# 04_POWER.net
KiCad netlist of a schematic drawn in Altium Designer
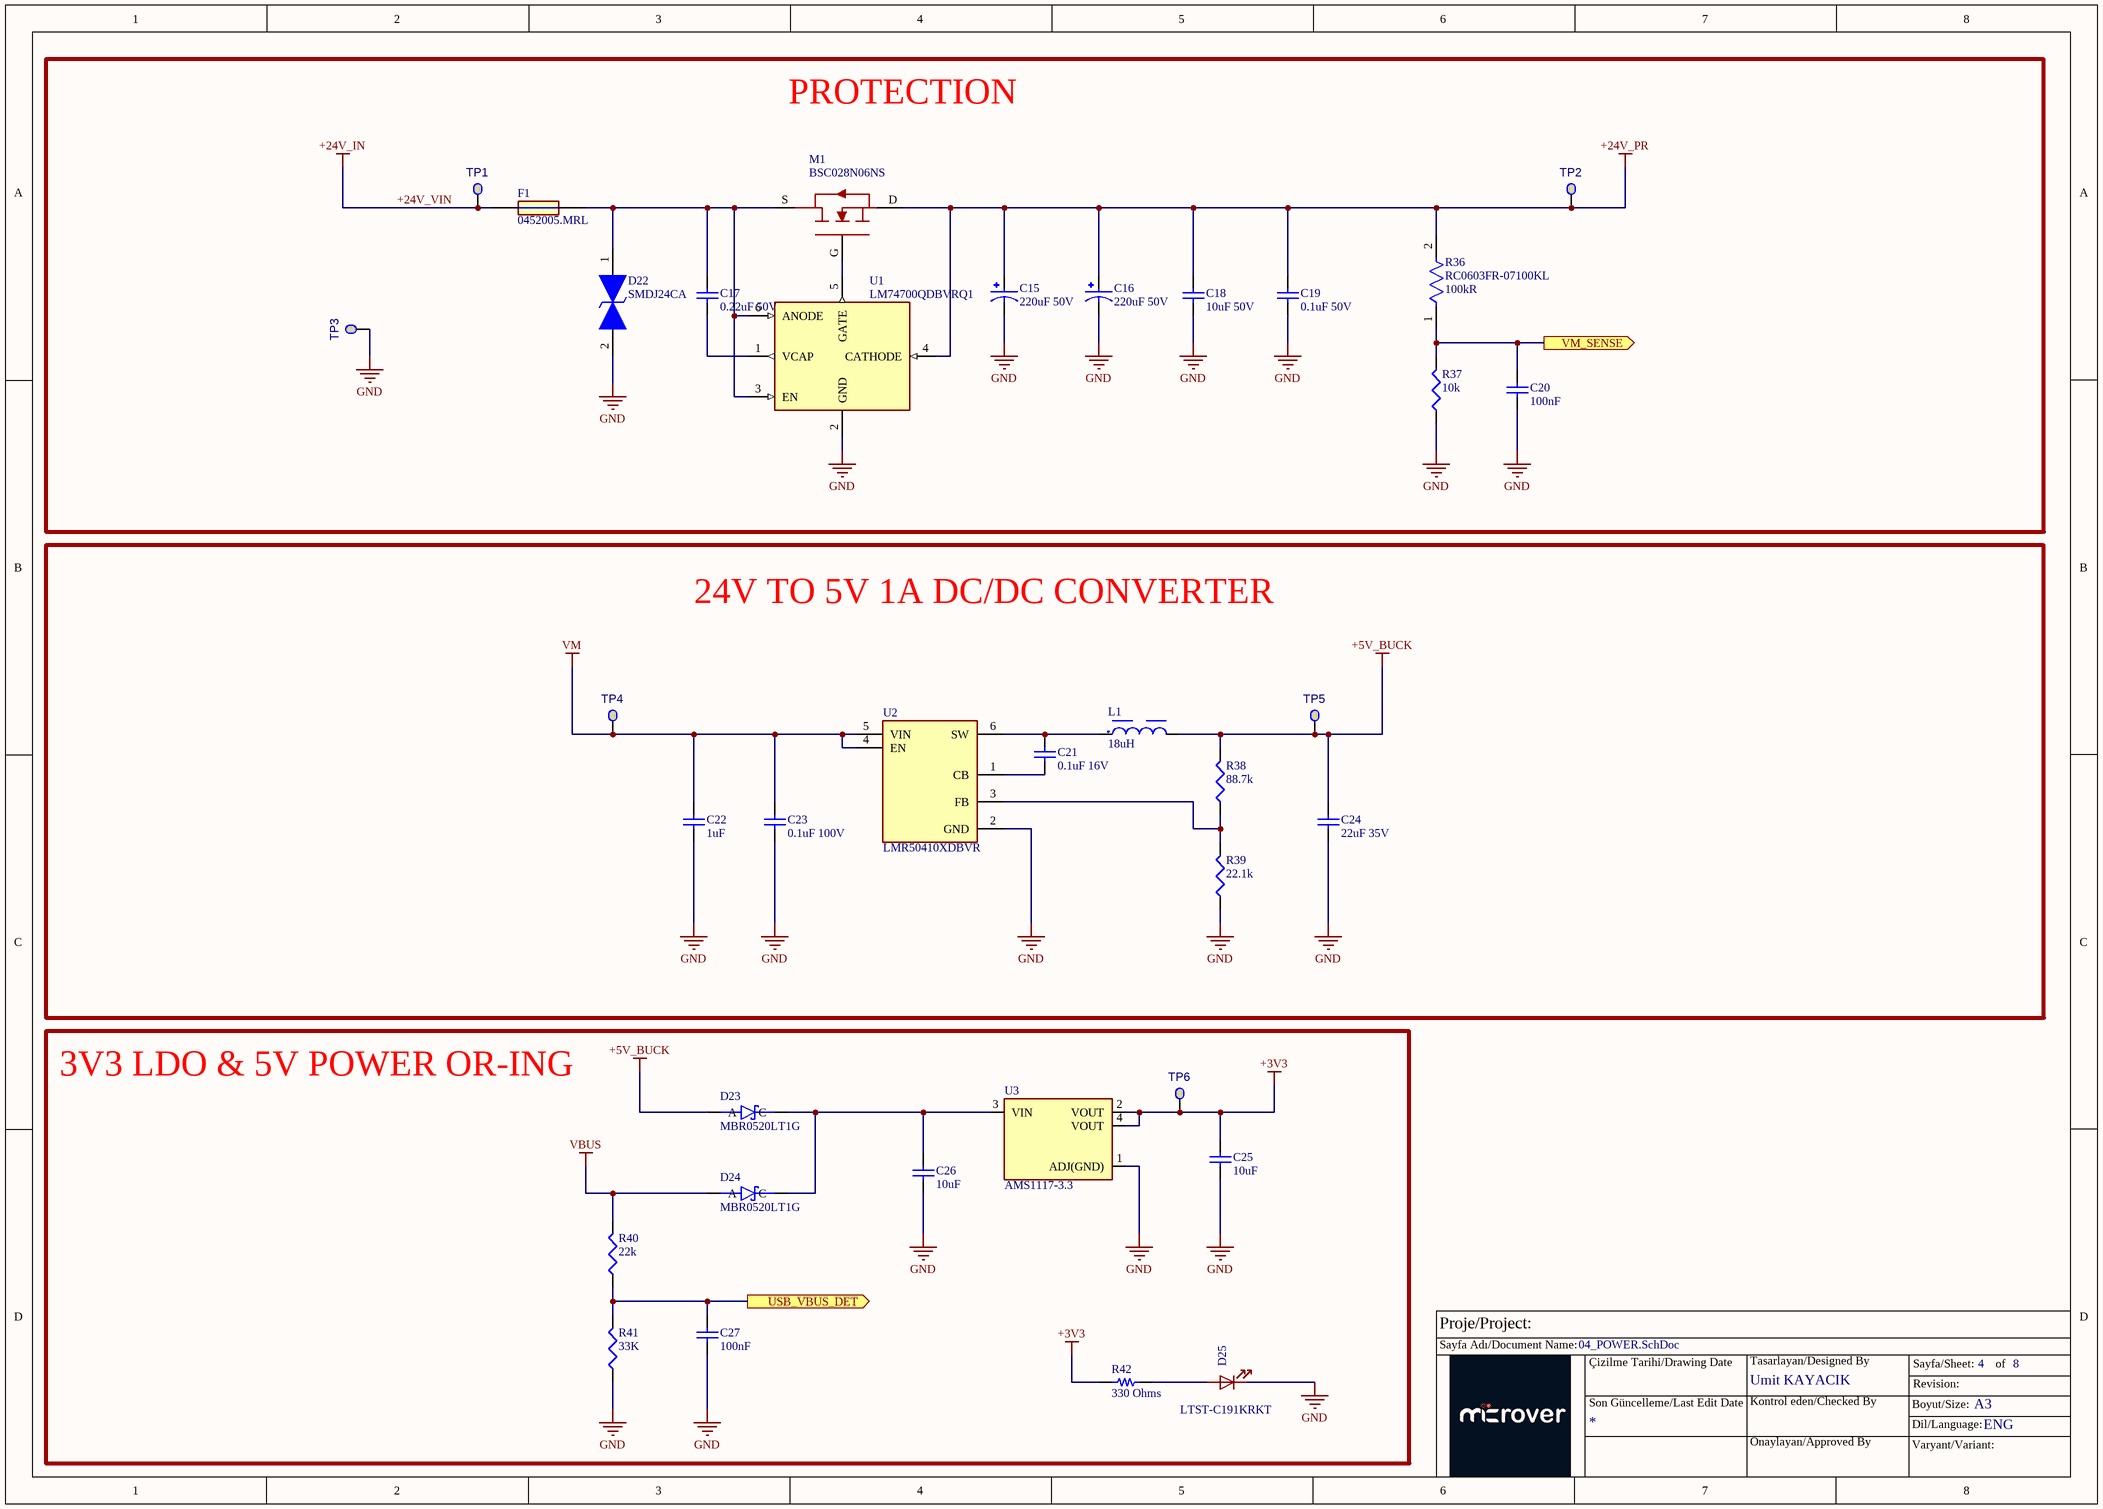
[diagram p0: 04_POWER.SchDoc]

(export (version "E")
  (design (tool "Eeschema 10.0.6"))
  (components
    (comp (ref "C15")
      (value "220uF 50V")
      (footprint "CAP_EEEFT1H221AV")
      (description "220 µF 50 V Aluminum Electrolytic Capacitors Radial, Can - SMD 180mOhm @ 100kHz 2000 Hrs @ 105°C")
      (fields
        (field (name "MANUFACTURER PART NUMBER") "EEE-FT1H221AV")
        (field (name "MF") "Panasonic Electronic Components")
      )
      (libsource (lib "HW_ADHERENT_LANECTRL_R1") (part "EEEFT1H221AV"))
    )
    (comp (ref "C16")
      (value "220uF 50V")
      (footprint "CAP_EEEFT1H221AV")
      (description "220 µF 50 V Aluminum Electrolytic Capacitors Radial, Can - SMD 180mOhm @ 100kHz 2000 Hrs @ 105°C")
      (fields
        (field (name "MANUFACTURER PART NUMBER") "EEE-FT1H221AV")
        (field (name "MF") "Panasonic Electronic Components")
      )
      (libsource (lib "HW_ADHERENT_LANECTRL_R1") (part "EEEFT1H221AV"))
    )
    (comp (ref "C17")
      (value "0.22uF 50V")
      (footprint "SMC0603")
      (description "0.22 µF ±10% 50V Ceramic Capacitor X7R 0603 (1608 Metric)")
      (fields
        (field (name "MANUFACTURER PART NUMBER") "GCM188R71H224KA64D")
        (field (name "Comment") "CAP CER 0.22UF 50V X7R 0603")
      )
      (libsource (lib "HW_ADHERENT_LANECTRL_R1") (part "CAP0603_0.22UF_50V"))
    )
    (comp (ref "C18")
      (value "10uF 50V")
      (footprint "SMC1206")
      (description "10 µF ±10% 50V Ceramic Capacitor X5R 1206 (3216 Metric)")
      (fields
        (field (name "MANUFACTURER PART NUMBER") "CL31A106KBHNNNE")
        (field (name "LCSC PART NUMBER") "C13585")
      )
      (libsource (lib "HW_ADHERENT_LANECTRL_R1") (part "CAP1206_10UF_50V"))
    )
    (comp (ref "C19")
      (value "0.1uF 50V")
      (footprint "SMC0603")
      (description "0.1 µF ±10% 50V Ceramic Capacitor X7R 0603 (1608 Metric)")
      (fields
        (field (name "MANUFACTURER PART NUMBER") "CL10B104KB8NNNL")
        (field (name "LCSC PART NUMBER") "C1591")
      )
      (libsource (lib "HW_ADHERENT_LANECTRL_R1") (part "CAP0603_0.1UF_50V_2"))
    )
    (comp (ref "C20")
      (value "100nF")
      (footprint "CAP0603")
      (description "0.1 µF ±10% 50V Ceramic Capacitor X7R 0603 (1608 Metric)")
      (fields
        (field (name "MANUFACTURER PART NUMBER") "CL10B104KA8NNNC")
        (field (name "LCSC PART NUMBER") "C1590")
      )
      (libsource (lib "HW_ADHERENT_LANECTRL_R1") (part "CAP0603_100nF"))
    )
    (comp (ref "C21")
      (value "0.1uF 16V")
      (footprint "CAP0603")
      (description "0.1 µF ±20% 16V Ceramic Capacitor X7R 0603 (1608 Metric)")
      (libsource (lib "HW_ADHERENT_LANECTRL_R1") (part "C0603C104M4RACTU"))
    )
    (comp (ref "C22")
      (value "1uF")
      (footprint "CAP0603")
      (description "CAP CER 1UF 50V X5R 0603")
      (fields (field (name "MANUFACTURER") "Taiyo Yuden"))
      (libsource (lib "HW_ADHERENT_LANECTRL_R1") (part "MSASU168SB5105MTNA01"))
    )
    (comp (ref "C23")
      (value "0.1uF 100V")
      (footprint "CAP0603")
      (description "CAP CER 0.1UF 100V X7R 0603")
      (libsource (lib "HW_ADHERENT_LANECTRL_R1") (part "GRM188R72A104KA35D"))
    )
    (comp (ref "C24")
      (value "22uF 35V")
      (footprint "CAP1206")
      (description "22 µF ±20% 35V Ceramic Capacitor X5R 1206 (3216 Metric)")
      (fields (field (name "MANUFACTURER PART NUMBER") "C3216X5R1V226M160AC"))
      (libsource (lib "HW_ADHERENT_LANECTRL_R1") (part "CAP1206_22uF_35V"))
    )
    (comp (ref "C25")
      (value "10uF")
      (footprint "CAP0603")
      (description "10 µF ±10% 25V Ceramic Capacitor X5R 0603 (1608 Metric)")
      (fields (field (name "MANUFACTURER PART NUMBER") "GRM188R61E106KA73J"))
      (libsource (lib "HW_ADHERENT_LANECTRL_R1") (part "CAP0603_10uF_25V"))
    )
    (comp (ref "C26")
      (value "10uF")
      (footprint "CAP0603")
      (description "10 µF ±10% 25V Ceramic Capacitor X5R 0603 (1608 Metric)")
      (fields (field (name "MANUFACTURER PART NUMBER") "GRM188R61E106KA73J"))
      (libsource (lib "HW_ADHERENT_LANECTRL_R1") (part "CAP0603_10uF_25V"))
    )
    (comp (ref "C27")
      (value "100nF")
      (footprint "CAP0603")
      (description "0.1 µF ±10% 50V Ceramic Capacitor X7R 0603 (1608 Metric)")
      (fields
        (field (name "MANUFACTURER PART NUMBER") "CL10B104KA8NNNC")
        (field (name "LCSC PART NUMBER") "C1590")
      )
      (libsource (lib "HW_ADHERENT_LANECTRL_R1") (part "CAP0603_100nF"))
    )
    (comp (ref "D22")
      (value "SMDJ24CA")
      (footprint "DIONM9059X262N")
      (description "38.9V Clamp 77.1A Ipp Tvs Diode Surface Mount DO-214AB (SMCJ)")
      (fields (field (name "MANUFACTURER") "Littelfuse Inc."))
      (libsource (lib "HW_ADHERENT_LANECTRL_R1") (part "SMDJ24CA"))
    )
    (comp (ref "D23")
      (value "MBR0520LT1G")
      (footprint "SOD3716X135N")
      (description "Diode 20 V 500mA Surface Mount SOD-123")
      (libsource (lib "HW_ADHERENT_LANECTRL_R1") (part "MBR0520LT1G"))
    )
    (comp (ref "D24")
      (value "MBR0520LT1G")
      (footprint "SOD3716X135N")
      (description "Diode 20 V 500mA Surface Mount SOD-123")
      (libsource (lib "HW_ADHERENT_LANECTRL_R1") (part "MBR0520LT1G"))
    )
    (comp (ref "D25")
      (value "LTST-C191KRKT")
      (footprint "LED0603")
      (description "LED RED CLEAR SMD")
      (fields (field (name "MANUFACTURER") "Lite-On Inc."))
      (libsource (lib "HW_ADHERENT_LANECTRL_R1") (part "LED_1"))
    )
    (comp (ref "F1")
      (value "0452005.MRL")
      (footprint "FUSC6127X294N")
      (description "FUSE BRD MNT 5A 125VAC/VDC 2SMD")
      (fields (field (name "MANUFACTURER") "Littelfuse"))
      (libsource (lib "HW_ADHERENT_LANECTRL_R1") (part "0452005.MRL"))
    )
    (comp (ref "L1")
      (value "18uH")
      (footprint "WE-LQS_6045")
      (description "18 µH Semi-Shielded Drum Core, Wirewound Inductor 2.2 A 81mOhm Nonstandard")
      (libsource (lib "HW_ADHERENT_LANECTRL_R1") (part "74404064180"))
    )
    (comp (ref "M1")
      (value "BSC028N06NS")
      (footprint "BSC028N06NS")
      (description "MOSFET'ler N-Ch 60V 100A TDSON-8 OptiMOS 3")
      (libsource (lib "HW_ADHERENT_LANECTRL_R1") (part "BSC028N06NS"))
    )
    (comp (ref "R36")
      (value "RC0603FR-07100KL")
      (footprint "FP-RC0603-0_55-MFG")
      (description "RES SMD 100K OHM 1% 1/10W 0603")
      (fields (field (name "RESISTANCE") "100kR") (field (name "TOLERANCE") "1%"))
      (libsource (lib "HW_ADHERENT_LANECTRL_R1") (part "CMP-2100-03662-2"))
    )
    (comp (ref "R37")
      (value "10k")
      (footprint "RES0603")
      (description "10 kOhms ±1% 0.125W, 1/8W Chip Resistor 0603 (1608 Metric) Anti-Sulfur Thin Film")
      (fields
        (field (name "MANUFACTURER PART NUMBER") "RNCP0603FTD10K0")
        (field (name "LCSC PART NUMBER") "C161803")
      )
      (libsource (lib "HW_ADHERENT_LANECTRL_R1") (part "RES0603_10K_%1_1"))
    )
    (comp (ref "R38")
      (value "88.7k")
      (footprint "RES0603")
      (description "88.7 kOhms ±1% 0.125W, 1/8W Chip Resistor 0603 (1608 Metric) Automotive AEC-Q200 Thick Film")
      (libsource (lib "HW_ADHERENT_LANECTRL_R1") (part "CRCW060388K7FKEA"))
    )
    (comp (ref "R39")
      (value "22.1k")
      (footprint "RES0603")
      (description "22.1 kOhms ±1% 0.1W, 1/10W Chip Resistor 0603 (1608 Metric) Moisture Resistant Thick Film")
      (libsource (lib "HW_ADHERENT_LANECTRL_R1") (part "RC0603FR-0722K1L"))
    )
    (comp (ref "R40")
      (value "22k")
      (footprint "SMR0603")
      (description "10 kOhms ±1% 0.1W, 1/10W Chip Resistor 0603 (1608 Metric) Moisture Resistant Thick Film")
      (fields
        (field (name "MANUFACTURER PART NUMBER") "RC0603FR-0722KL")
        (field (name "LCSC PART NUMBER") "C114065")
      )
      (libsource (lib "HW_ADHERENT_LANECTRL_R1") (part "RES0603_22K_%1"))
    )
    (comp (ref "R41")
      (value "33K")
      (footprint "SMR0603")
      (description "33 kOhms ±1% 0.1W, 1/10W Chip Resistor 0603 (1608 Metric) Moisture Resistant Thick Film")
      (fields
        (field (name "MANUFACTURER PART NUMBER") "RC0603FR-0733KL")
        (field (name "LCSC PART NUMBER") "C126359")
      )
      (libsource (lib "HW_ADHERENT_LANECTRL_R1") (part "RES0603_33K_%1"))
    )
    (comp (ref "R42")
      (value "330 Ohms")
      (footprint "RES 0603_1608")
      (description "RES SMD 330 OHM 1% 1/5W 0603")
      (fields
        (field (name "PART NUMBER") "CRGH0603F330R")
        (field (name "MANUFACTURER") "TE Connectivity Passive Product")
      )
      (libsource (lib "HW_ADHERENT_LANECTRL_R1") (part "CRGH0603F330R"))
    )
    (comp (ref "TP1")
      (value "Testpoint")
      (footprint "SMD_Ø1.5mm")
      (libsource (lib "HW_ADHERENT_LANECTRL_R1") (part "TEST PAD SMT 10MIL X 20MIL"))
    )
    (comp (ref "TP2")
      (value "Testpoint")
      (footprint "SMD_Ø1.5mm")
      (libsource (lib "HW_ADHERENT_LANECTRL_R1") (part "TEST PAD SMT 10MIL X 20MIL"))
    )
    (comp (ref "TP3")
      (value "Testpoint")
      (footprint "SMD_Ø1.5mm")
      (libsource (lib "HW_ADHERENT_LANECTRL_R1") (part "TEST PAD SMT 10MIL X 20MIL"))
    )
    (comp (ref "TP4")
      (value "Testpoint")
      (footprint "SMD_Ø1.5mm")
      (libsource (lib "HW_ADHERENT_LANECTRL_R1") (part "TEST PAD SMT 10MIL X 20MIL"))
    )
    (comp (ref "TP5")
      (value "Testpoint")
      (footprint "SMD_Ø1.5mm")
      (libsource (lib "HW_ADHERENT_LANECTRL_R1") (part "TEST PAD SMT 10MIL X 20MIL"))
    )
    (comp (ref "TP6")
      (value "Testpoint")
      (footprint "SMD_Ø1.5mm")
      (libsource (lib "HW_ADHERENT_LANECTRL_R1") (part "TEST PAD SMT 10MIL X 20MIL"))
    )
    (comp (ref "U1")
      (value "LM74700QDBVRQ1")
      (footprint "SOT95P280X145-6N/LM74700QDBVRQ1")
      (description "OR Controller N+1 ORing Controller N-Channel 1:1 SOT-23-6")
      (libsource (lib "HW_ADHERENT_LANECTRL_R1") (part "LM74700QDBVRQ1"))
    )
    (comp (ref "U2")
      (value "LMR50410XDBVR")
      (footprint "SOT95P280X145-6N/")
      (description "Buck Switching Regulator IC Positive Adjustable 1V 1 Output 1A SOT-23-6")
      (libsource (lib "HW_ADHERENT_LANECTRL_R1") (part "LMR50410XDBVR"))
    )
    (comp (ref "U3")
      (value "AMS1117-3.3")
      (footprint "SOT-223-4_L6.5-W3.5-P2.30-LS7.0-BR")
      (description "Linear Voltage Regulator IC Positive Fixed 1 Output 1A SOT-223-3L")
      (fields (field (name "MANUFACTURER") "UMW"))
      (libsource (lib "HW_ADHERENT_LANECTRL_R1") (part "AMS1117-3.3"))
    )
  )
  (nets
    (net (code "1") (name "+3V3") (class "Default")
      (node (ref "C25") (pin "2") (pinfunction "2_2") (pintype "passive"))
      (node (ref "R42") (pin "1") (pinfunction "1_1") (pintype "passive"))
      (node (ref "TP6") (pin "1") (pinfunction "P1_1") (pintype "passive"))
      (node (ref "U3") (pin "2") (pinfunction "VOUT_2") (pintype "passive"))
      (node (ref "U3") (pin "4") (pinfunction "VOUT_4") (pintype "passive"))
    )
    (net (code "2") (name "+5V_BUCK") (class "Default")
      (node (ref "C24") (pin "2") (pinfunction "2_2") (pintype "passive"))
      (node (ref "D23") (pin "A") (pinfunction "A_A") (pintype "passive"))
      (node (ref "L1") (pin "2") (pinfunction "2_2") (pintype "passive"))
      (node (ref "R38") (pin "2") (pinfunction "2_2") (pintype "passive"))
      (node (ref "TP5") (pin "1") (pinfunction "P1_1") (pintype "passive"))
    )
    (net (code "3") (name "+24V_IN") (class "Default")
      (node (ref "F1") (pin "1") (pinfunction "1_1") (pintype "passive"))
      (node (ref "TP1") (pin "1") (pinfunction "P1_1") (pintype "passive"))
    )
    (net (code "4") (name "+24V_PR") (class "Default")
      (node (ref "C15") (pin "1") (pinfunction "1_1") (pintype "passive"))
      (node (ref "C16") (pin "1") (pinfunction "1_1") (pintype "passive"))
      (node (ref "C18") (pin "2") (pinfunction "2_2") (pintype "passive"))
      (node (ref "C19") (pin "2") (pinfunction "2_2") (pintype "passive"))
      (node (ref "M1") (pin "D") (pinfunction "D_D") (pintype "passive"))
      (node (ref "R36") (pin "2") (pinfunction "2_2") (pintype "passive"))
      (node (ref "TP2") (pin "1") (pinfunction "P1_1") (pintype "passive"))
      (node (ref "U1") (pin "4") (pinfunction "CATHODE_4") (pintype "input"))
    )
    (net (code "5") (name "/USB_VBUS_DET") (class "Default")
      (node (ref "C27") (pin "2") (pinfunction "2_2") (pintype "passive"))
      (node (ref "R40") (pin "1") (pinfunction "1_1") (pintype "passive"))
      (node (ref "R41") (pin "2") (pinfunction "2_2") (pintype "passive"))
    )
    (net (code "6") (name "/VM_SENSE") (class "Default")
      (node (ref "C20") (pin "2") (pinfunction "2_2") (pintype "passive"))
      (node (ref "R36") (pin "1") (pinfunction "1_1") (pintype "passive"))
      (node (ref "R37") (pin "2") (pinfunction "2_2") (pintype "passive"))
    )
    (net (code "7") (name "GND") (class "Default")
      (node (ref "C15") (pin "2") (pinfunction "2_2") (pintype "passive"))
      (node (ref "C16") (pin "2") (pinfunction "2_2") (pintype "passive"))
      (node (ref "C18") (pin "1") (pinfunction "1_1") (pintype "passive"))
      (node (ref "C19") (pin "1") (pinfunction "1_1") (pintype "passive"))
      (node (ref "C20") (pin "1") (pinfunction "1_1") (pintype "passive"))
      (node (ref "C22") (pin "1") (pinfunction "1_1") (pintype "passive"))
      (node (ref "C23") (pin "1") (pinfunction "1_1") (pintype "passive"))
      (node (ref "C24") (pin "1") (pinfunction "1_1") (pintype "passive"))
      (node (ref "C25") (pin "1") (pinfunction "1_1") (pintype "passive"))
      (node (ref "C26") (pin "1") (pinfunction "1_1") (pintype "passive"))
      (node (ref "C27") (pin "1") (pinfunction "1_1") (pintype "passive"))
      (node (ref "D22") (pin "2") (pinfunction "2_2") (pintype "passive"))
      (node (ref "D25") (pin "2") (pinfunction "K_2") (pintype "passive"))
      (node (ref "R37") (pin "1") (pinfunction "1_1") (pintype "passive"))
      (node (ref "R39") (pin "1") (pinfunction "1_1") (pintype "passive"))
      (node (ref "R41") (pin "1") (pinfunction "1_1") (pintype "passive"))
      (node (ref "TP3") (pin "1") (pinfunction "P1_1") (pintype "passive"))
      (node (ref "U1") (pin "2") (pinfunction "GND_2") (pintype "power_in"))
      (node (ref "U2") (pin "2") (pinfunction "GND_2") (pintype "passive"))
      (node (ref "U3") (pin "1") (pinfunction "ADJ(GND)_1") (pintype "passive"))
    )
    (net (code "8") (name "Net-(D25-A)") (class "Default")
      (node (ref "D25") (pin "1") (pinfunction "A_1") (pintype "passive"))
      (node (ref "R42") (pin "2") (pinfunction "2_2") (pintype "passive"))
    )
    (net (code "9") (name "Net-(U1-ANODE)") (class "Default")
      (node (ref "C17") (pin "2") (pinfunction "2_2") (pintype "passive"))
      (node (ref "D22") (pin "1") (pinfunction "1_1") (pintype "passive"))
      (node (ref "F1") (pin "2") (pinfunction "2_2") (pintype "passive"))
      (node (ref "M1") (pin "S") (pinfunction "S_S") (pintype "passive"))
      (node (ref "U1") (pin "3") (pinfunction "EN_3") (pintype "input"))
      (node (ref "U1") (pin "6") (pinfunction "ANODE_6") (pintype "input"))
    )
    (net (code "10") (name "Net-(U1-GATE)") (class "Default")
      (node (ref "M1") (pin "G") (pinfunction "G_G") (pintype "passive"))
      (node (ref "U1") (pin "5") (pinfunction "GATE_5") (pintype "output"))
    )
    (net (code "11") (name "Net-(U1-VCAP)") (class "Default")
      (node (ref "C17") (pin "1") (pinfunction "1_1") (pintype "passive"))
      (node (ref "U1") (pin "1") (pinfunction "VCAP_1") (pintype "output"))
    )
    (net (code "12") (name "Net-(U2-CB)") (class "Default")
      (node (ref "C21") (pin "1") (pinfunction "1_1") (pintype "passive"))
      (node (ref "U2") (pin "1") (pinfunction "CB_1") (pintype "passive"))
    )
    (net (code "13") (name "Net-(U2-FB)") (class "Default")
      (node (ref "R38") (pin "1") (pinfunction "1_1") (pintype "passive"))
      (node (ref "R39") (pin "2") (pinfunction "2_2") (pintype "passive"))
      (node (ref "U2") (pin "3") (pinfunction "FB_3") (pintype "passive"))
    )
    (net (code "14") (name "Net-(U2-SW)") (class "Default")
      (node (ref "C21") (pin "2") (pinfunction "2_2") (pintype "passive"))
      (node (ref "L1") (pin "1") (pinfunction "1_1") (pintype "passive"))
      (node (ref "U2") (pin "6") (pinfunction "SW_6") (pintype "passive"))
    )
    (net (code "15") (name "Net-(U3-VIN)") (class "Default")
      (node (ref "C26") (pin "2") (pinfunction "2_2") (pintype "passive"))
      (node (ref "D23") (pin "C") (pinfunction "C_C") (pintype "passive"))
      (node (ref "D24") (pin "C") (pinfunction "C_C") (pintype "passive"))
      (node (ref "U3") (pin "3") (pinfunction "VIN_3") (pintype "passive"))
    )
    (net (code "16") (name "VBUS") (class "Default")
      (node (ref "D24") (pin "A") (pinfunction "A_A") (pintype "passive"))
      (node (ref "R40") (pin "2") (pinfunction "2_2") (pintype "passive"))
    )
    (net (code "17") (name "VM") (class "Default")
      (node (ref "C22") (pin "2") (pinfunction "2_2") (pintype "passive"))
      (node (ref "C23") (pin "2") (pinfunction "2_2") (pintype "passive"))
      (node (ref "TP4") (pin "1") (pinfunction "P1_1") (pintype "passive"))
      (node (ref "U2") (pin "4") (pinfunction "EN_4") (pintype "passive"))
      (node (ref "U2") (pin "5") (pinfunction "VIN_5") (pintype "power_in"))
    )
  )
)
